# bridge_board_rony.net
KiCad netlist of a schematic drawn in EAGLE
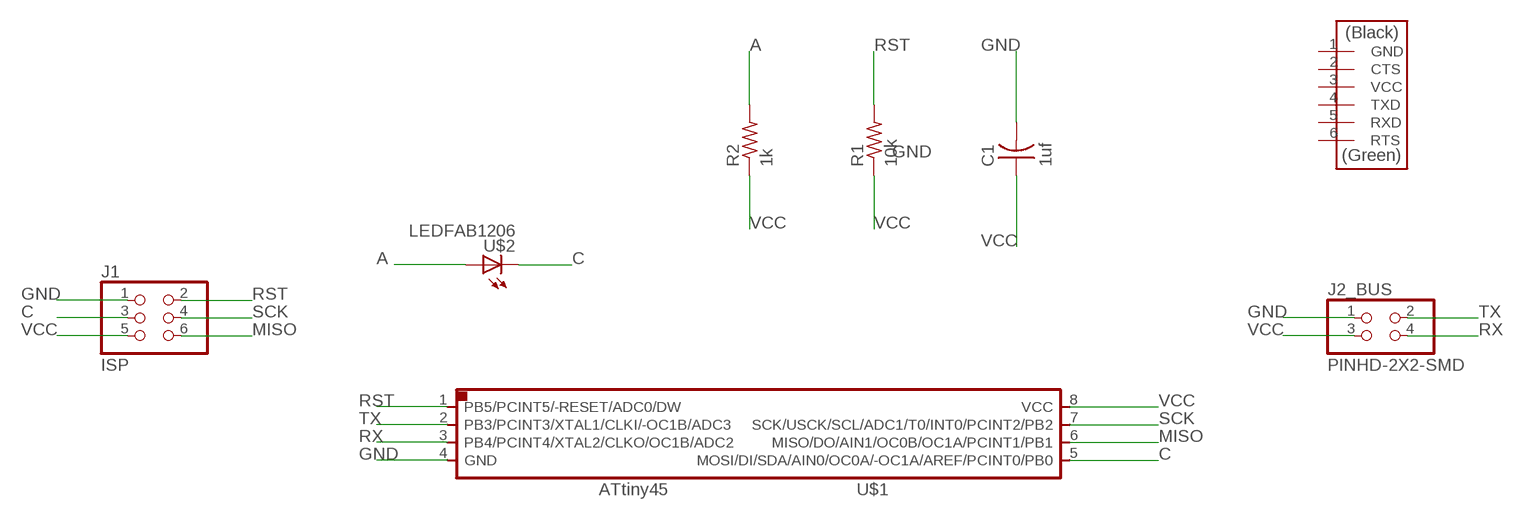
[diagram p0: schematic, sheet 1]

(export (version "E")
  (design (tool "Eeschema 10.0.6"))
  (components
    (comp (ref "C1")
      (value "1uf")
      (footprint "eagle-import:C1206FAB")
      (libsource (lib "eagle-import") (part "CAP-US1206FAB"))
    )
    (comp (ref "J1")
      (value "ISP")
      (footprint "eagle-import:2X03SMD")
      (libsource (lib "eagle-import") (part "PINHD-2X3-SMD"))
    )
    (comp (ref "J2_BUS")
      (value "PINHD-2X2-SMD")
      (footprint "eagle-import:2X02SMD")
      (libsource (lib "eagle-import") (part "PINHD-2X2-SMD"))
    )
    (comp (ref "R1")
      (value "10k")
      (footprint "eagle-import:R1206FAB")
      (libsource (lib "eagle-import") (part "RES-US1206FAB"))
    )
    (comp (ref "R2")
      (value "1k")
      (footprint "eagle-import:R1206FAB")
      (libsource (lib "eagle-import") (part "RES-US1206FAB"))
    )
    (comp (ref "U$1")
      (value "ATTINY45SI")
      (footprint "eagle-import:SOIC8")
      (libsource (lib "eagle-import") (part "ATTINY45SI"))
    )
    (comp (ref "U$2")
      (value "LEDFAB1206")
      (footprint "eagle-import:LED1206FAB")
      (libsource (lib "eagle-import") (part "LEDFAB1206"))
    )
    (comp (ref "U$3")
      (value "FTDI-SMD-HEADER")
      (footprint "eagle-import:1X06SMD")
      (libsource (lib "eagle-import") (part "FTDI-SMD-HEADER"))
    )
  )
  (nets
    (net (code "1") (name "/A") (class "Default")
      (node (ref "R2") (pin "2") (pinfunction "2_2") (pintype "passive"))
      (node (ref "U$2") (pin "1") (pinfunction "A_1") (pintype "passive"))
    )
    (net (code "2") (name "/C") (class "Default")
      (node (ref "J1") (pin "3") (pinfunction "3_3") (pintype "passive"))
      (node (ref "U$1") (pin "5") (pinfunction "MOSI/DI/SDA/AIN0/OC0A/-OC1A/AREF/PCINT0/PB0_5") (pintype "bidirectional"))
      (node (ref "U$2") (pin "2") (pinfunction "C_2") (pintype "passive"))
    )
    (net (code "3") (name "/GND") (class "Default")
      (node (ref "C1") (pin "2") (pinfunction "2_2") (pintype "passive"))
      (node (ref "J1") (pin "1") (pinfunction "1_1") (pintype "passive"))
      (node (ref "J2_BUS") (pin "1") (pinfunction "1_1") (pintype "passive"))
      (node (ref "U$1") (pin "4") (pinfunction "GND_4") (pintype "bidirectional"))
    )
    (net (code "4") (name "/MISO") (class "Default")
      (node (ref "J1") (pin "6") (pinfunction "6_6") (pintype "passive"))
      (node (ref "U$1") (pin "6") (pinfunction "MISO/DO/AIN1/OC0B/OC1A/PCINT1/PB1_6") (pintype "bidirectional"))
    )
    (net (code "5") (name "/RST") (class "Default")
      (node (ref "J1") (pin "2") (pinfunction "2_2") (pintype "passive"))
      (node (ref "R1") (pin "2") (pinfunction "2_2") (pintype "passive"))
      (node (ref "U$1") (pin "1") (pinfunction "PB5/PCINT5/-RESET/ADC0/DW_1") (pintype "bidirectional"))
    )
    (net (code "6") (name "/RX") (class "Default")
      (node (ref "J2_BUS") (pin "4") (pinfunction "4_4") (pintype "passive"))
      (node (ref "U$1") (pin "3") (pinfunction "PB4/PCINT4/XTAL2/CLKO/OC1B/ADC2_3") (pintype "bidirectional"))
    )
    (net (code "7") (name "/SCK") (class "Default")
      (node (ref "J1") (pin "4") (pinfunction "4_4") (pintype "passive"))
      (node (ref "U$1") (pin "7") (pinfunction "SCK/USCK/SCL/ADC1/T0/INT0/PCINT2/PB2_7") (pintype "bidirectional"))
    )
    (net (code "8") (name "/TX") (class "Default")
      (node (ref "J2_BUS") (pin "2") (pinfunction "2_2") (pintype "passive"))
      (node (ref "U$1") (pin "2") (pinfunction "PB3/PCINT3/XTAL1/CLKI/-OC1B/ADC3_2") (pintype "bidirectional"))
    )
    (net (code "9") (name "/VCC") (class "Default")
      (node (ref "C1") (pin "1") (pinfunction "1_1") (pintype "passive"))
      (node (ref "J1") (pin "5") (pinfunction "5_5") (pintype "passive"))
      (node (ref "J2_BUS") (pin "3") (pinfunction "3_3") (pintype "passive"))
      (node (ref "R1") (pin "1") (pinfunction "1_1") (pintype "passive"))
      (node (ref "R2") (pin "1") (pinfunction "1_1") (pintype "passive"))
      (node (ref "U$1") (pin "8") (pinfunction "VCC_8") (pintype "bidirectional"))
    )
    (net (code "10") (name "unconnected-(U$3-CTS-Pad2)") (class "Default")
      (node (ref "U$3") (pin "2") (pinfunction "CTS_2") (pintype "bidirectional"))
    )
    (net (code "11") (name "unconnected-(U$3-GND-Pad1)") (class "Default")
      (node (ref "U$3") (pin "1") (pinfunction "GND_1") (pintype "bidirectional"))
    )
    (net (code "12") (name "unconnected-(U$3-RTS-Pad6)") (class "Default")
      (node (ref "U$3") (pin "6") (pinfunction "RTS_6") (pintype "bidirectional"))
    )
    (net (code "13") (name "unconnected-(U$3-RXD-Pad5)") (class "Default")
      (node (ref "U$3") (pin "5") (pinfunction "RXD_5") (pintype "bidirectional"))
    )
    (net (code "14") (name "unconnected-(U$3-TXD-Pad4)") (class "Default")
      (node (ref "U$3") (pin "4") (pinfunction "TXD_4") (pintype "bidirectional"))
    )
    (net (code "15") (name "unconnected-(U$3-VCC-Pad3)") (class "Default")
      (node (ref "U$3") (pin "3") (pinfunction "VCC_3") (pintype "bidirectional"))
    )
  )
)
